# Board_I.net
KiCad netlist of a schematic drawn in EAGLE
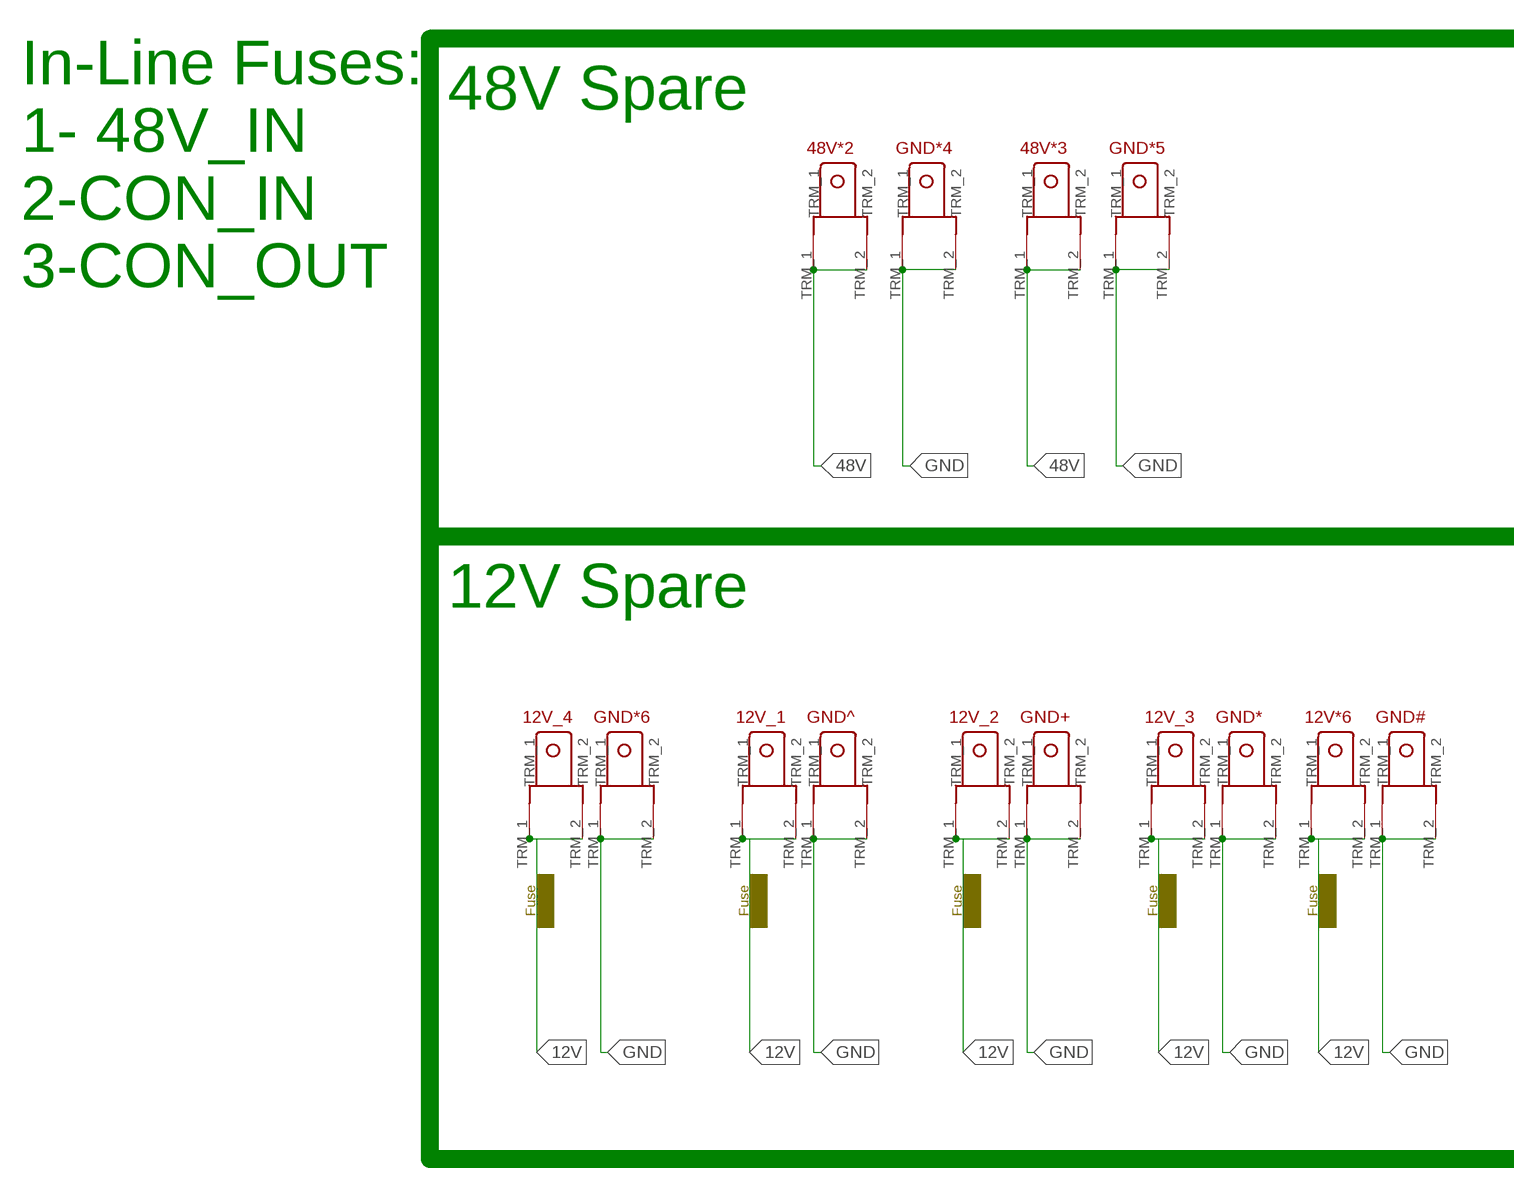
[diagram p0: schematic, sheet 1, part 1 of 2]
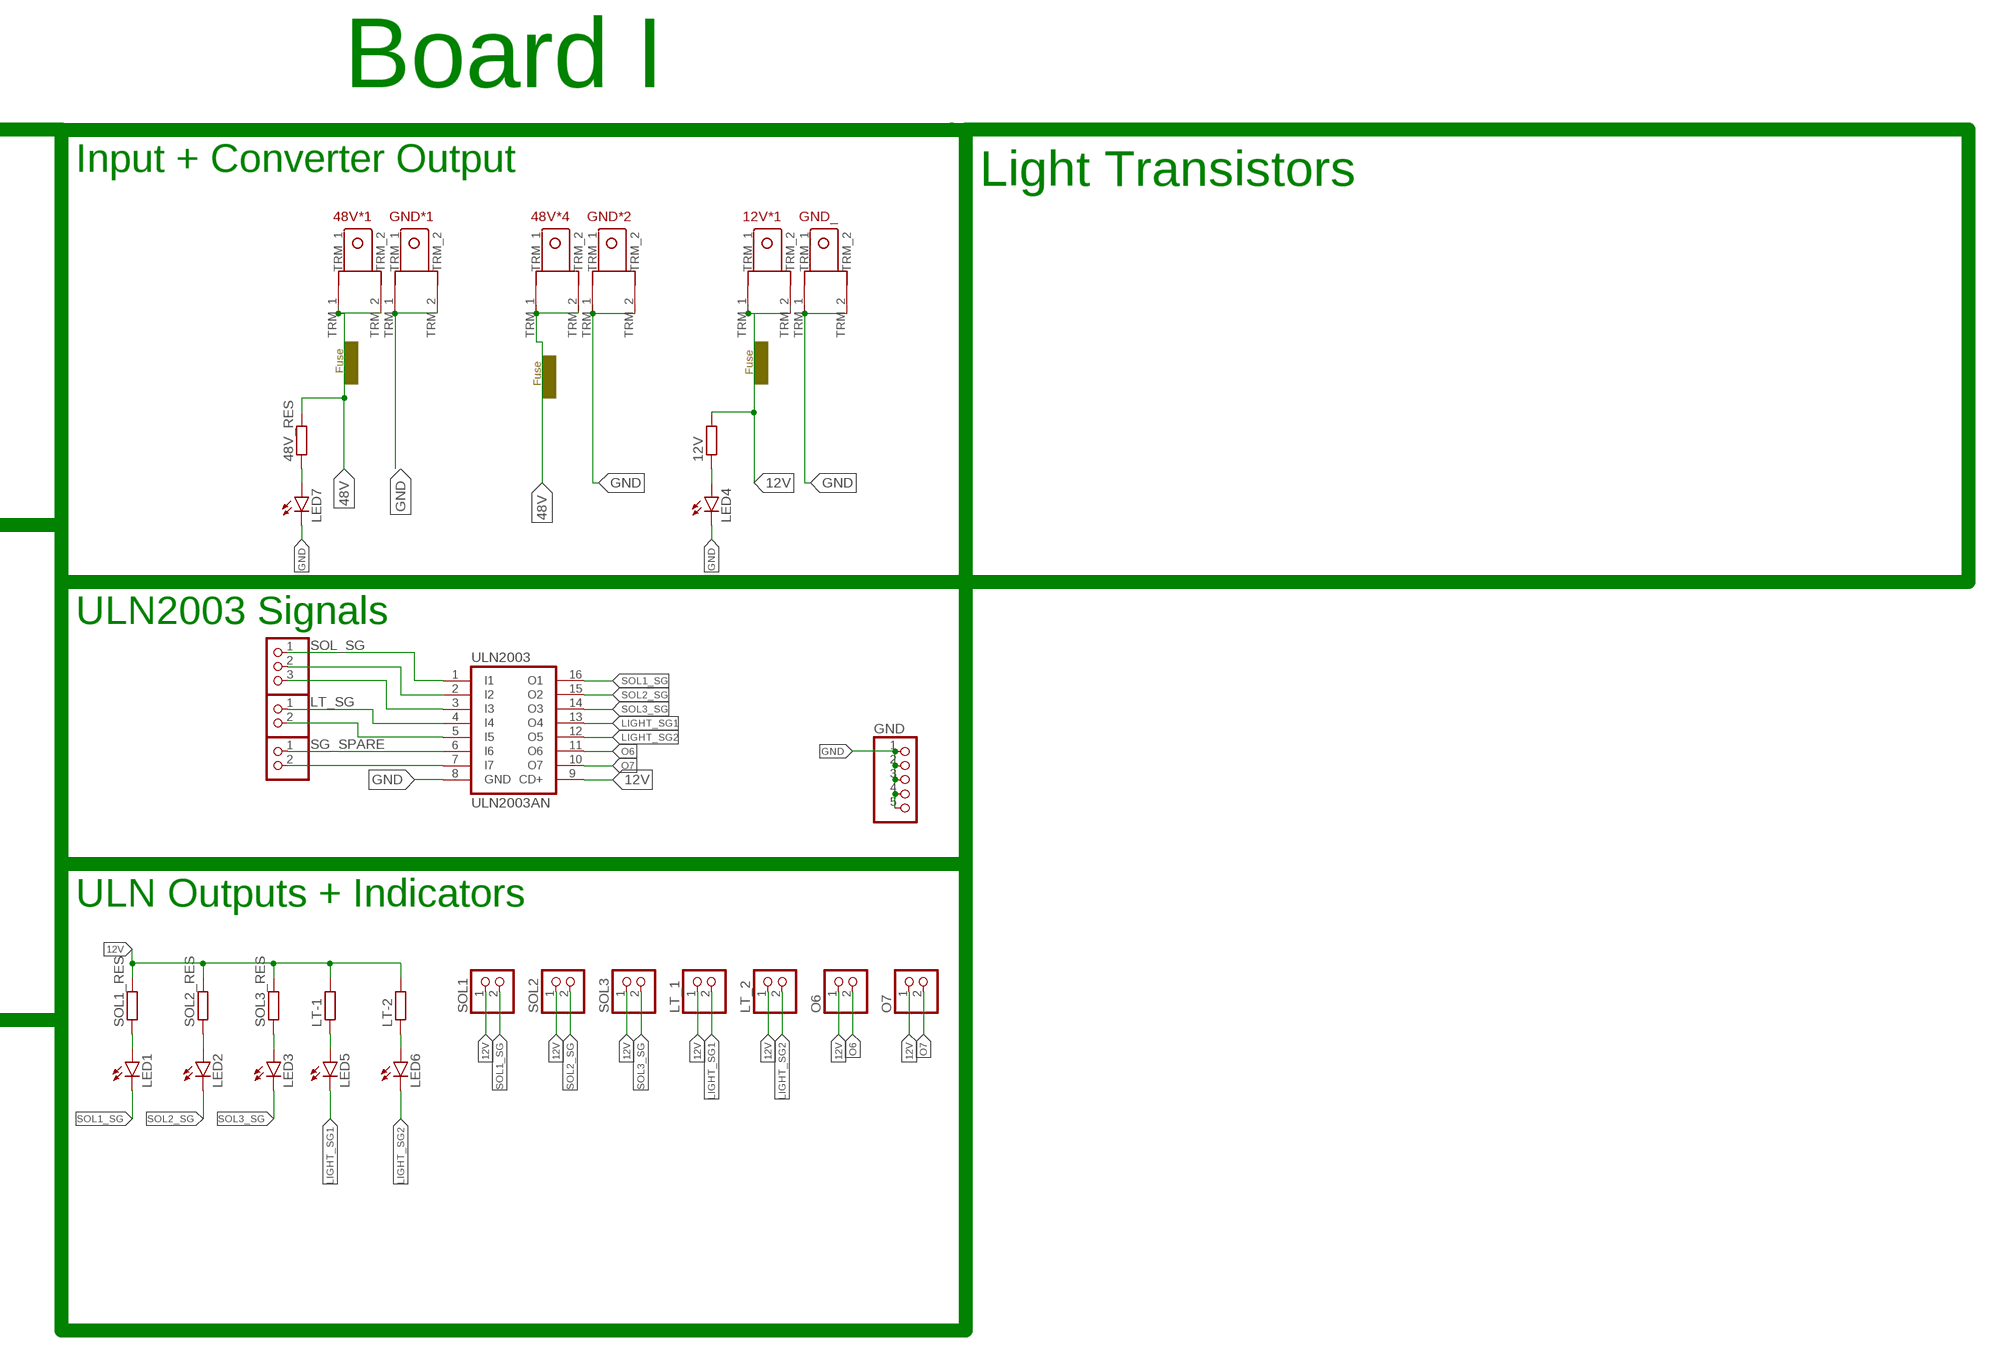
[diagram p1: schematic, sheet 1, part 2 of 2]

(export (version "E")
  (design (tool "Eeschema 10.0.6"))
  (components
    (comp (ref "12V")
      (value "RESISTOR")
      (footprint "eagle-import:0207_10")
      (libsource (lib "eagle-import") (part "RESISTOR"))
    )
    (comp (ref "12V*1")
      (value "TERMINAL_EDITED")
      (footprint "eagle-import:TERMINAL_EDITED")
      (libsource (lib "eagle-import") (part "TERMINAL_EDITED"))
    )
    (comp (ref "12V*6")
      (value "TERMINAL_EDITED")
      (footprint "eagle-import:TERMINAL_EDITED")
      (libsource (lib "eagle-import") (part "TERMINAL_EDITED"))
    )
    (comp (ref "12V_1")
      (value "TERMINAL_EDITED")
      (footprint "eagle-import:TERMINAL_EDITED")
      (libsource (lib "eagle-import") (part "TERMINAL_EDITED"))
    )
    (comp (ref "12V_2")
      (value "TERMINAL_EDITED")
      (footprint "eagle-import:TERMINAL_EDITED")
      (libsource (lib "eagle-import") (part "TERMINAL_EDITED"))
    )
    (comp (ref "12V_3")
      (value "TERMINAL_EDITED")
      (footprint "eagle-import:TERMINAL_EDITED")
      (libsource (lib "eagle-import") (part "TERMINAL_EDITED"))
    )
    (comp (ref "12V_4")
      (value "TERMINAL_EDITED")
      (footprint "eagle-import:TERMINAL_EDITED")
      (libsource (lib "eagle-import") (part "TERMINAL_EDITED"))
    )
    (comp (ref "48V*1")
      (value "TERMINAL_EDITED")
      (footprint "eagle-import:TERMINAL_EDITED")
      (libsource (lib "eagle-import") (part "TERMINAL_EDITED"))
    )
    (comp (ref "48V*2")
      (value "TERMINAL_EDITED")
      (footprint "eagle-import:TERMINAL_EDITED")
      (libsource (lib "eagle-import") (part "TERMINAL_EDITED"))
    )
    (comp (ref "48V*3")
      (value "TERMINAL_EDITED")
      (footprint "eagle-import:TERMINAL_EDITED")
      (libsource (lib "eagle-import") (part "TERMINAL_EDITED"))
    )
    (comp (ref "48V*4")
      (value "TERMINAL_EDITED")
      (footprint "eagle-import:TERMINAL_EDITED")
      (libsource (lib "eagle-import") (part "TERMINAL_EDITED"))
    )
    (comp (ref "48V_RES")
      (value "RESISTOR")
      (footprint "eagle-import:0207_10")
      (libsource (lib "eagle-import") (part "RESISTOR"))
    )
    (comp (ref "GND")
      (value "PINHD-1X5")
      (footprint "eagle-import:1X05")
      (libsource (lib "eagle-import") (part "PINHD-1X5"))
    )
    (comp (ref "GND#")
      (value "TERMINAL_EDITED")
      (footprint "eagle-import:TERMINAL_EDITED")
      (libsource (lib "eagle-import") (part "TERMINAL_EDITED"))
    )
    (comp (ref "GND*")
      (value "TERMINAL_EDITED")
      (footprint "eagle-import:TERMINAL_EDITED")
      (libsource (lib "eagle-import") (part "TERMINAL_EDITED"))
    )
    (comp (ref "GND*1")
      (value "TERMINAL_EDITED")
      (footprint "eagle-import:TERMINAL_EDITED")
      (libsource (lib "eagle-import") (part "TERMINAL_EDITED"))
    )
    (comp (ref "GND*2")
      (value "TERMINAL_EDITED")
      (footprint "eagle-import:TERMINAL_EDITED")
      (libsource (lib "eagle-import") (part "TERMINAL_EDITED"))
    )
    (comp (ref "GND*4")
      (value "TERMINAL_EDITED")
      (footprint "eagle-import:TERMINAL_EDITED")
      (libsource (lib "eagle-import") (part "TERMINAL_EDITED"))
    )
    (comp (ref "GND*5")
      (value "TERMINAL_EDITED")
      (footprint "eagle-import:TERMINAL_EDITED")
      (libsource (lib "eagle-import") (part "TERMINAL_EDITED"))
    )
    (comp (ref "GND*6")
      (value "TERMINAL_EDITED")
      (footprint "eagle-import:TERMINAL_EDITED")
      (libsource (lib "eagle-import") (part "TERMINAL_EDITED"))
    )
    (comp (ref "GND+")
      (value "TERMINAL_EDITED")
      (footprint "eagle-import:TERMINAL_EDITED")
      (libsource (lib "eagle-import") (part "TERMINAL_EDITED"))
    )
    (comp (ref "GND^")
      (value "TERMINAL_EDITED")
      (footprint "eagle-import:TERMINAL_EDITED")
      (libsource (lib "eagle-import") (part "TERMINAL_EDITED"))
    )
    (comp (ref "GND_")
      (value "TERMINAL_EDITED")
      (footprint "eagle-import:TERMINAL_EDITED")
      (libsource (lib "eagle-import") (part "TERMINAL_EDITED"))
    )
    (comp (ref "LED1")
      (value "LED5MM")
      (footprint "eagle-import:LED5MM")
      (libsource (lib "eagle-import") (part "LED5MM"))
    )
    (comp (ref "LED2")
      (value "LED5MM")
      (footprint "eagle-import:LED5MM")
      (libsource (lib "eagle-import") (part "LED5MM"))
    )
    (comp (ref "LED3")
      (value "LED5MM")
      (footprint "eagle-import:LED5MM")
      (libsource (lib "eagle-import") (part "LED5MM"))
    )
    (comp (ref "LED4")
      (value "LED5MM")
      (footprint "eagle-import:LED5MM")
      (libsource (lib "eagle-import") (part "LED5MM"))
    )
    (comp (ref "LED5")
      (value "LED5MM")
      (footprint "eagle-import:LED5MM")
      (libsource (lib "eagle-import") (part "LED5MM"))
    )
    (comp (ref "LED6")
      (value "LED5MM")
      (footprint "eagle-import:LED5MM")
      (libsource (lib "eagle-import") (part "LED5MM"))
    )
    (comp (ref "LED7")
      (value "LED5MM")
      (footprint "eagle-import:LED5MM")
      (libsource (lib "eagle-import") (part "LED5MM"))
    )
    (comp (ref "LT-1")
      (value "RESISTOR")
      (footprint "eagle-import:0207_10")
      (libsource (lib "eagle-import") (part "RESISTOR"))
    )
    (comp (ref "LT-2")
      (value "RESISTOR")
      (footprint "eagle-import:0207_10")
      (libsource (lib "eagle-import") (part "RESISTOR"))
    )
    (comp (ref "LT_1")
      (value "PINHD-1X2")
      (footprint "eagle-import:1X02")
      (libsource (lib "eagle-import") (part "PINHD-1X2"))
    )
    (comp (ref "LT_2")
      (value "PINHD-1X2")
      (footprint "eagle-import:1X02")
      (libsource (lib "eagle-import") (part "PINHD-1X2"))
    )
    (comp (ref "LT_SG")
      (value "PINHD-1X2")
      (footprint "eagle-import:1X02")
      (libsource (lib "eagle-import") (part "PINHD-1X2"))
    )
    (comp (ref "O6")
      (value "PINHD-1X2")
      (footprint "eagle-import:1X02")
      (libsource (lib "eagle-import") (part "PINHD-1X2"))
    )
    (comp (ref "O7")
      (value "PINHD-1X2")
      (footprint "eagle-import:1X02")
      (libsource (lib "eagle-import") (part "PINHD-1X2"))
    )
    (comp (ref "SG_SPARE")
      (value "PINHD-1X2")
      (footprint "eagle-import:1X02")
      (libsource (lib "eagle-import") (part "PINHD-1X2"))
    )
    (comp (ref "SOL1")
      (value "PINHD-1X2")
      (footprint "eagle-import:1X02")
      (libsource (lib "eagle-import") (part "PINHD-1X2"))
    )
    (comp (ref "SOL1_RES")
      (value "RESISTOR")
      (footprint "eagle-import:0207_10")
      (libsource (lib "eagle-import") (part "RESISTOR"))
    )
    (comp (ref "SOL2")
      (value "PINHD-1X2")
      (footprint "eagle-import:1X02")
      (libsource (lib "eagle-import") (part "PINHD-1X2"))
    )
    (comp (ref "SOL2_RES")
      (value "RESISTOR")
      (footprint "eagle-import:0207_10")
      (libsource (lib "eagle-import") (part "RESISTOR"))
    )
    (comp (ref "SOL3")
      (value "PINHD-1X2")
      (footprint "eagle-import:1X02")
      (libsource (lib "eagle-import") (part "PINHD-1X2"))
    )
    (comp (ref "SOL3_RES")
      (value "RESISTOR")
      (footprint "eagle-import:0207_10")
      (libsource (lib "eagle-import") (part "RESISTOR"))
    )
    (comp (ref "SOL_SG")
      (value "PINHD-1X3")
      (footprint "eagle-import:1X03")
      (libsource (lib "eagle-import") (part "PINHD-1X3"))
    )
    (comp (ref "ULN2003")
      (value "ULN2003AN")
      (footprint "eagle-import:DIL16")
      (libsource (lib "eagle-import") (part "ULN2003AN"))
    )
  )
  (nets
    (net (code "1") (name "12V") (class "Default")
      (node (ref "12V") (pin "2") (pinfunction "2_2") (pintype "passive"))
      (node (ref "12V*1") (pin "TRM_1") (pinfunction "TRM_1_TRM_1") (pintype "bidirectional"))
      (node (ref "12V*1") (pin "TRM_2") (pinfunction "TRM_2_TRM_2") (pintype "bidirectional"))
      (node (ref "12V*6") (pin "TRM_1") (pinfunction "TRM_1_TRM_1") (pintype "bidirectional"))
      (node (ref "12V*6") (pin "TRM_2") (pinfunction "TRM_2_TRM_2") (pintype "bidirectional"))
      (node (ref "12V_1") (pin "TRM_1") (pinfunction "TRM_1_TRM_1") (pintype "bidirectional"))
      (node (ref "12V_1") (pin "TRM_2") (pinfunction "TRM_2_TRM_2") (pintype "bidirectional"))
      (node (ref "12V_2") (pin "TRM_1") (pinfunction "TRM_1_TRM_1") (pintype "bidirectional"))
      (node (ref "12V_2") (pin "TRM_2") (pinfunction "TRM_2_TRM_2") (pintype "bidirectional"))
      (node (ref "12V_3") (pin "TRM_1") (pinfunction "TRM_1_TRM_1") (pintype "bidirectional"))
      (node (ref "12V_3") (pin "TRM_2") (pinfunction "TRM_2_TRM_2") (pintype "bidirectional"))
      (node (ref "12V_4") (pin "TRM_1") (pinfunction "TRM_1_TRM_1") (pintype "bidirectional"))
      (node (ref "12V_4") (pin "TRM_2") (pinfunction "TRM_2_TRM_2") (pintype "bidirectional"))
      (node (ref "LT-1") (pin "2") (pinfunction "2_2") (pintype "passive"))
      (node (ref "LT-2") (pin "2") (pinfunction "2_2") (pintype "passive"))
      (node (ref "LT_1") (pin "1") (pinfunction "1_1") (pintype "passive"))
      (node (ref "LT_2") (pin "1") (pinfunction "1_1") (pintype "passive"))
      (node (ref "O6") (pin "1") (pinfunction "1_1") (pintype "passive"))
      (node (ref "O7") (pin "1") (pinfunction "1_1") (pintype "passive"))
      (node (ref "SOL1") (pin "1") (pinfunction "1_1") (pintype "passive"))
      (node (ref "SOL1_RES") (pin "2") (pinfunction "2_2") (pintype "passive"))
      (node (ref "SOL2") (pin "1") (pinfunction "1_1") (pintype "passive"))
      (node (ref "SOL2_RES") (pin "2") (pinfunction "2_2") (pintype "passive"))
      (node (ref "SOL3") (pin "1") (pinfunction "1_1") (pintype "passive"))
      (node (ref "SOL3_RES") (pin "2") (pinfunction "2_2") (pintype "passive"))
      (node (ref "ULN2003") (pin "9") (pinfunction "CD+_9") (pintype "passive"))
    )
    (net (code "2") (name "48V") (class "Default")
      (node (ref "48V*1") (pin "TRM_1") (pinfunction "TRM_1_TRM_1") (pintype "bidirectional"))
      (node (ref "48V*1") (pin "TRM_2") (pinfunction "TRM_2_TRM_2") (pintype "bidirectional"))
      (node (ref "48V*2") (pin "TRM_1") (pinfunction "TRM_1_TRM_1") (pintype "bidirectional"))
      (node (ref "48V*2") (pin "TRM_2") (pinfunction "TRM_2_TRM_2") (pintype "bidirectional"))
      (node (ref "48V*3") (pin "TRM_1") (pinfunction "TRM_1_TRM_1") (pintype "bidirectional"))
      (node (ref "48V*3") (pin "TRM_2") (pinfunction "TRM_2_TRM_2") (pintype "bidirectional"))
      (node (ref "48V*4") (pin "TRM_1") (pinfunction "TRM_1_TRM_1") (pintype "bidirectional"))
      (node (ref "48V*4") (pin "TRM_2") (pinfunction "TRM_2_TRM_2") (pintype "bidirectional"))
      (node (ref "48V_RES") (pin "2") (pinfunction "2_2") (pintype "passive"))
    )
    (net (code "3") (name "GND") (class "Default")
      (node (ref "GND") (pin "1") (pinfunction "1_1") (pintype "passive"))
      (node (ref "GND") (pin "2") (pinfunction "2_2") (pintype "passive"))
      (node (ref "GND") (pin "3") (pinfunction "3_3") (pintype "passive"))
      (node (ref "GND") (pin "4") (pinfunction "4_4") (pintype "passive"))
      (node (ref "GND") (pin "5") (pinfunction "5_5") (pintype "passive"))
      (node (ref "GND#") (pin "TRM_1") (pinfunction "TRM_1_TRM_1") (pintype "bidirectional"))
      (node (ref "GND#") (pin "TRM_2") (pinfunction "TRM_2_TRM_2") (pintype "bidirectional"))
      (node (ref "GND*") (pin "TRM_1") (pinfunction "TRM_1_TRM_1") (pintype "bidirectional"))
      (node (ref "GND*") (pin "TRM_2") (pinfunction "TRM_2_TRM_2") (pintype "bidirectional"))
      (node (ref "GND*1") (pin "TRM_1") (pinfunction "TRM_1_TRM_1") (pintype "bidirectional"))
      (node (ref "GND*1") (pin "TRM_2") (pinfunction "TRM_2_TRM_2") (pintype "bidirectional"))
      (node (ref "GND*2") (pin "TRM_1") (pinfunction "TRM_1_TRM_1") (pintype "bidirectional"))
      (node (ref "GND*2") (pin "TRM_2") (pinfunction "TRM_2_TRM_2") (pintype "bidirectional"))
      (node (ref "GND*4") (pin "TRM_1") (pinfunction "TRM_1_TRM_1") (pintype "bidirectional"))
      (node (ref "GND*4") (pin "TRM_2") (pinfunction "TRM_2_TRM_2") (pintype "bidirectional"))
      (node (ref "GND*5") (pin "TRM_1") (pinfunction "TRM_1_TRM_1") (pintype "bidirectional"))
      (node (ref "GND*5") (pin "TRM_2") (pinfunction "TRM_2_TRM_2") (pintype "bidirectional"))
      (node (ref "GND*6") (pin "TRM_1") (pinfunction "TRM_1_TRM_1") (pintype "bidirectional"))
      (node (ref "GND*6") (pin "TRM_2") (pinfunction "TRM_2_TRM_2") (pintype "bidirectional"))
      (node (ref "GND+") (pin "TRM_1") (pinfunction "TRM_1_TRM_1") (pintype "bidirectional"))
      (node (ref "GND+") (pin "TRM_2") (pinfunction "TRM_2_TRM_2") (pintype "bidirectional"))
      (node (ref "GND^") (pin "TRM_1") (pinfunction "TRM_1_TRM_1") (pintype "bidirectional"))
      (node (ref "GND^") (pin "TRM_2") (pinfunction "TRM_2_TRM_2") (pintype "bidirectional"))
      (node (ref "GND_") (pin "TRM_1") (pinfunction "TRM_1_TRM_1") (pintype "bidirectional"))
      (node (ref "GND_") (pin "TRM_2") (pinfunction "TRM_2_TRM_2") (pintype "bidirectional"))
      (node (ref "LED4") (pin "K") (pinfunction "C_K") (pintype "passive"))
      (node (ref "LED7") (pin "K") (pinfunction "C_K") (pintype "passive"))
      (node (ref "ULN2003") (pin "8") (pinfunction "GND_8") (pintype "power_in"))
    )
    (net (code "4") (name "LIGHT_SG1") (class "Default")
      (node (ref "LED5") (pin "K") (pinfunction "C_K") (pintype "passive"))
      (node (ref "LT_1") (pin "2") (pinfunction "2_2") (pintype "passive"))
      (node (ref "ULN2003") (pin "13") (pinfunction "O4_13") (pintype "open_collector"))
    )
    (net (code "5") (name "LIGHT_SG2") (class "Default")
      (node (ref "LED6") (pin "K") (pinfunction "C_K") (pintype "passive"))
      (node (ref "LT_2") (pin "2") (pinfunction "2_2") (pintype "passive"))
      (node (ref "ULN2003") (pin "12") (pinfunction "O5_12") (pintype "open_collector"))
    )
    (net (code "6") (name "Net-(12V-Pad1)") (class "Default")
      (node (ref "12V") (pin "1") (pinfunction "1_1") (pintype "passive"))
      (node (ref "LED4") (pin "A") (pinfunction "A_A") (pintype "passive"))
    )
    (net (code "7") (name "Net-(48V_RES-Pad1)") (class "Default")
      (node (ref "48V_RES") (pin "1") (pinfunction "1_1") (pintype "passive"))
      (node (ref "LED7") (pin "A") (pinfunction "A_A") (pintype "passive"))
    )
    (net (code "8") (name "Net-(LED1-PadA)") (class "Default")
      (node (ref "LED1") (pin "A") (pinfunction "A_A") (pintype "passive"))
      (node (ref "SOL1_RES") (pin "1") (pinfunction "1_1") (pintype "passive"))
    )
    (net (code "9") (name "Net-(LED2-PadA)") (class "Default")
      (node (ref "LED2") (pin "A") (pinfunction "A_A") (pintype "passive"))
      (node (ref "SOL2_RES") (pin "1") (pinfunction "1_1") (pintype "passive"))
    )
    (net (code "10") (name "Net-(LED3-PadA)") (class "Default")
      (node (ref "LED3") (pin "A") (pinfunction "A_A") (pintype "passive"))
      (node (ref "SOL3_RES") (pin "1") (pinfunction "1_1") (pintype "passive"))
    )
    (net (code "11") (name "Net-(LED5-PadA)") (class "Default")
      (node (ref "LED5") (pin "A") (pinfunction "A_A") (pintype "passive"))
      (node (ref "LT-1") (pin "1") (pinfunction "1_1") (pintype "passive"))
    )
    (net (code "12") (name "Net-(LED6-PadA)") (class "Default")
      (node (ref "LED6") (pin "A") (pinfunction "A_A") (pintype "passive"))
      (node (ref "LT-2") (pin "1") (pinfunction "1_1") (pintype "passive"))
    )
    (net (code "13") (name "Net-(ULN2003-I1)") (class "Default")
      (node (ref "SOL_SG") (pin "1") (pinfunction "1_1") (pintype "passive"))
      (node (ref "ULN2003") (pin "1") (pinfunction "I1_1") (pintype "input"))
    )
    (net (code "14") (name "Net-(ULN2003-I2)") (class "Default")
      (node (ref "SOL_SG") (pin "2") (pinfunction "2_2") (pintype "passive"))
      (node (ref "ULN2003") (pin "2") (pinfunction "I2_2") (pintype "input"))
    )
    (net (code "15") (name "Net-(ULN2003-I3)") (class "Default")
      (node (ref "SOL_SG") (pin "3") (pinfunction "3_3") (pintype "passive"))
      (node (ref "ULN2003") (pin "3") (pinfunction "I3_3") (pintype "input"))
    )
    (net (code "16") (name "Net-(ULN2003-I4)") (class "Default")
      (node (ref "LT_SG") (pin "1") (pinfunction "1_1") (pintype "passive"))
      (node (ref "ULN2003") (pin "4") (pinfunction "I4_4") (pintype "input"))
    )
    (net (code "17") (name "Net-(ULN2003-I5)") (class "Default")
      (node (ref "LT_SG") (pin "2") (pinfunction "2_2") (pintype "passive"))
      (node (ref "ULN2003") (pin "5") (pinfunction "I5_5") (pintype "input"))
    )
    (net (code "18") (name "Net-(ULN2003-I6)") (class "Default")
      (node (ref "SG_SPARE") (pin "1") (pinfunction "1_1") (pintype "passive"))
      (node (ref "ULN2003") (pin "6") (pinfunction "I6_6") (pintype "input"))
    )
    (net (code "19") (name "Net-(ULN2003-I7)") (class "Default")
      (node (ref "SG_SPARE") (pin "2") (pinfunction "2_2") (pintype "passive"))
      (node (ref "ULN2003") (pin "7") (pinfunction "I7_7") (pintype "input"))
    )
    (net (code "20") (name "O6") (class "Default")
      (node (ref "O6") (pin "2") (pinfunction "2_2") (pintype "passive"))
      (node (ref "ULN2003") (pin "11") (pinfunction "O6_11") (pintype "open_collector"))
    )
    (net (code "21") (name "O7") (class "Default")
      (node (ref "O7") (pin "2") (pinfunction "2_2") (pintype "passive"))
      (node (ref "ULN2003") (pin "10") (pinfunction "O7_10") (pintype "open_collector"))
    )
    (net (code "22") (name "SOL1_SG") (class "Default")
      (node (ref "LED1") (pin "K") (pinfunction "C_K") (pintype "passive"))
      (node (ref "SOL1") (pin "2") (pinfunction "2_2") (pintype "passive"))
      (node (ref "ULN2003") (pin "16") (pinfunction "O1_16") (pintype "open_collector"))
    )
    (net (code "23") (name "SOL2_SG") (class "Default")
      (node (ref "LED2") (pin "K") (pinfunction "C_K") (pintype "passive"))
      (node (ref "SOL2") (pin "2") (pinfunction "2_2") (pintype "passive"))
      (node (ref "ULN2003") (pin "15") (pinfunction "O2_15") (pintype "open_collector"))
    )
    (net (code "24") (name "SOL3_SG") (class "Default")
      (node (ref "LED3") (pin "K") (pinfunction "C_K") (pintype "passive"))
      (node (ref "SOL3") (pin "2") (pinfunction "2_2") (pintype "passive"))
      (node (ref "ULN2003") (pin "14") (pinfunction "O3_14") (pintype "open_collector"))
    )
  )
)
